# Adafruit_96x64_RGB_OLED_Breakout_v2_0.net
KiCad netlist of a schematic drawn in EAGLE
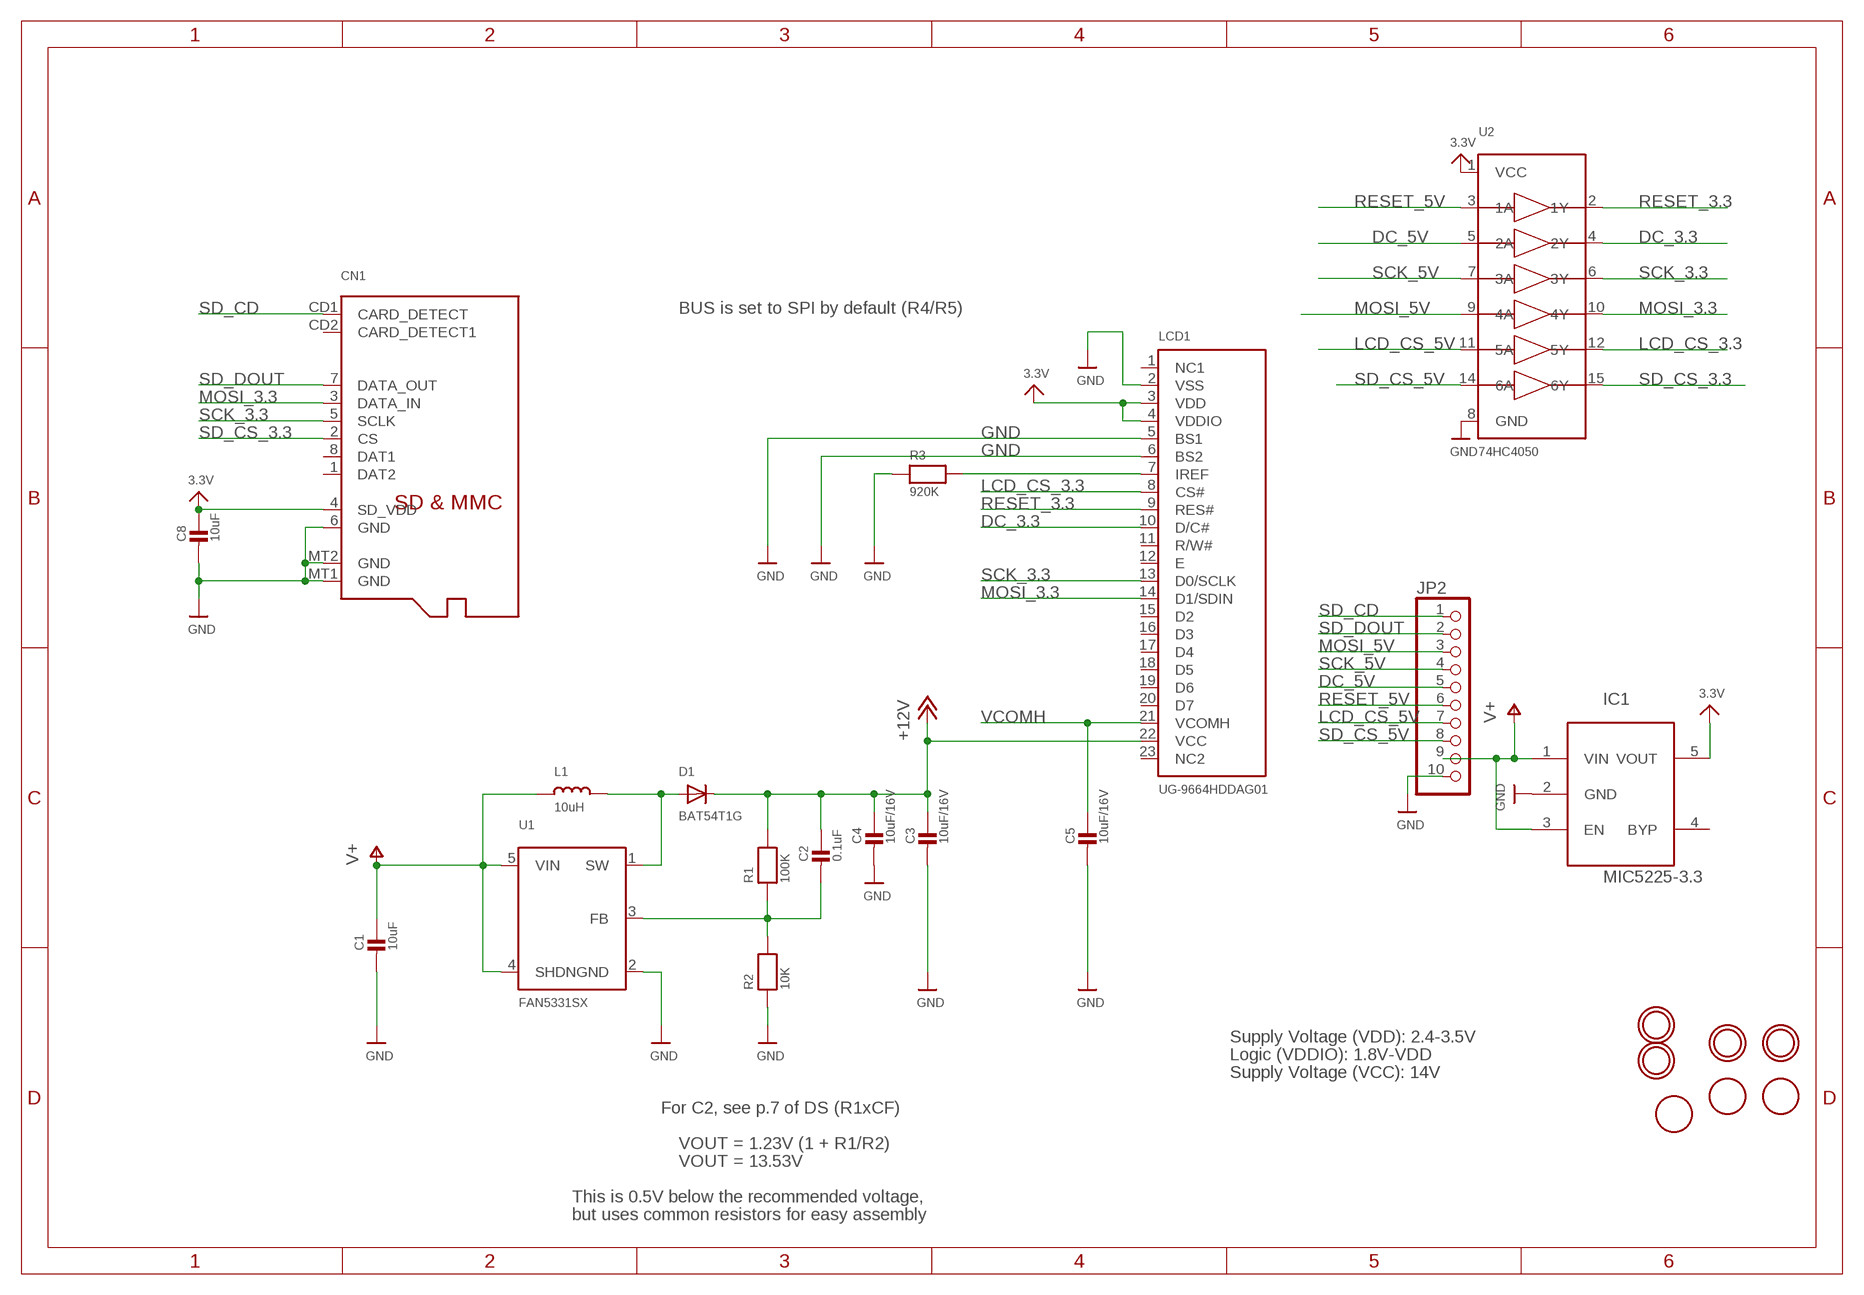
[diagram p0: schematic, sheet 1]

(export (version "E")
  (design (tool "Eeschema 10.0.6"))
  (components
    (comp (ref "C1")
      (value "10uF")
      (footprint "eagle-import:0805")
      (libsource (lib "eagle-import") (part "CAP_CERAMIC0805"))
    )
    (comp (ref "C2")
      (value "0.1uF")
      (footprint "eagle-import:0805")
      (libsource (lib "eagle-import") (part "CAP_CERAMIC0805"))
    )
    (comp (ref "C3")
      (value "10uF/16V")
      (footprint "eagle-import:0805")
      (libsource (lib "eagle-import") (part "CAP_CERAMIC0805"))
    )
    (comp (ref "C4")
      (value "10uF/16V")
      (footprint "eagle-import:0805")
      (libsource (lib "eagle-import") (part "CAP_CERAMIC0805"))
    )
    (comp (ref "C5")
      (value "10uF/16V")
      (footprint "eagle-import:0805")
      (libsource (lib "eagle-import") (part "CAP_CERAMIC0805"))
    )
    (comp (ref "C8")
      (value "10uF")
      (footprint "eagle-import:0805")
      (libsource (lib "eagle-import") (part "CAP_CERAMIC0805"))
    )
    (comp (ref "CN1")
      (value "MICROSD")
      (footprint "eagle-import:MICROSD")
      (libsource (lib "eagle-import") (part "MICROSD"))
    )
    (comp (ref "D1")
      (value "BAT54T1G")
      (footprint "eagle-import:SOD-123")
      (libsource (lib "eagle-import") (part "DIODESOD-123"))
    )
    (comp (ref "IC1")
      (value "MIC5225-3.3")
      (footprint "eagle-import:SOT23-5L")
      (libsource (lib "eagle-import") (part "LP298XS"))
    )
    (comp (ref "JP2")
      (value "HEADER-1X10THICKER")
      (footprint "eagle-import:1X10_ROUND_76")
      (libsource (lib "eagle-import") (part "HEADER-1X10THICKER"))
    )
    (comp (ref "L1")
      (value "10uH")
      (footprint "eagle-import:INDUCTOR_1007")
      (libsource (lib "eagle-import") (part "INDUCTOR"))
    )
    (comp (ref "LCD1")
      (value "UG-9664HDDAG01")
      (footprint "eagle-import:UG-9664HDDAG01_WRAPAROUND")
      (libsource (lib "eagle-import") (part "DISP_OLED_UG-9664HDDAG01WRAPAROUND"))
    )
    (comp (ref "R1")
      (value "100K")
      (footprint "eagle-import:0805")
      (libsource (lib "eagle-import") (part "RESISTOR0805"))
    )
    (comp (ref "R2")
      (value "10K")
      (footprint "eagle-import:0805")
      (libsource (lib "eagle-import") (part "RESISTOR0805"))
    )
    (comp (ref "R3")
      (value "920K")
      (footprint "eagle-import:0805")
      (libsource (lib "eagle-import") (part "RESISTOR0805"))
    )
    (comp (ref "U$9")
      (value "MOUNTINGHOLE2.5")
      (footprint "eagle-import:MOUNTINGHOLE_2.5_PLATED")
      (libsource (lib "eagle-import") (part "MOUNTINGHOLE2.5"))
    )
    (comp (ref "U$10")
      (value "MOUNTINGHOLE2.5")
      (footprint "eagle-import:MOUNTINGHOLE_2.5_PLATED")
      (libsource (lib "eagle-import") (part "MOUNTINGHOLE2.5"))
    )
    (comp (ref "U$11")
      (value "MOUNTINGHOLE2.5")
      (footprint "eagle-import:MOUNTINGHOLE_2.5_PLATED")
      (libsource (lib "eagle-import") (part "MOUNTINGHOLE2.5"))
    )
    (comp (ref "U$12")
      (value "FIDUCIAL")
      (footprint "eagle-import:FIDUCIAL_1MM")
      (libsource (lib "eagle-import") (part "FIDUCIAL"))
    )
    (comp (ref "U$13")
      (value "FIDUCIAL")
      (footprint "eagle-import:FIDUCIAL_1MM")
      (libsource (lib "eagle-import") (part "FIDUCIAL"))
    )
    (comp (ref "U$15")
      (value "MOUNTINGHOLE2.5")
      (footprint "eagle-import:MOUNTINGHOLE_2.5_PLATED")
      (libsource (lib "eagle-import") (part "MOUNTINGHOLE2.5"))
    )
    (comp (ref "U$16")
      (value "FIDUCIAL")
      (footprint "eagle-import:FIDUCIAL_1MM")
      (libsource (lib "eagle-import") (part "FIDUCIAL"))
    )
    (comp (ref "U1")
      (value "FAN5331SX")
      (footprint "eagle-import:SOT23-5")
      (libsource (lib "eagle-import") (part "FAN5331"))
    )
    (comp (ref "U2")
      (value "74HC4050")
      (footprint "eagle-import:SOIC16")
      (libsource (lib "eagle-import") (part "74HC4050D"))
    )
  )
  (nets
    (net (code "1") (name "+12V") (class "Default")
      (node (ref "C2") (pin "1") (pinfunction "P$1_1") (pintype "passive"))
      (node (ref "C3") (pin "1") (pinfunction "P$1_1") (pintype "passive"))
      (node (ref "C4") (pin "1") (pinfunction "P$1_1") (pintype "passive"))
      (node (ref "D1") (pin "C") (pinfunction "C_C") (pintype "passive"))
      (node (ref "LCD1") (pin "22") (pinfunction "VCC_22") (pintype "bidirectional"))
      (node (ref "R1") (pin "2") (pinfunction "2_2") (pintype "passive"))
    )
    (net (code "2") (name "/DC_3.3") (class "Default")
      (node (ref "LCD1") (pin "10") (pinfunction "D/C#_10") (pintype "bidirectional"))
      (node (ref "U2") (pin "4") (pinfunction "2Y_4") (pintype "bidirectional"))
    )
    (net (code "3") (name "/DC_5V") (class "Default")
      (node (ref "JP2") (pin "5") (pinfunction "5_5") (pintype "passive"))
      (node (ref "U2") (pin "5") (pinfunction "2A_5") (pintype "bidirectional"))
    )
    (net (code "4") (name "/LCD_CS_3.3") (class "Default")
      (node (ref "LCD1") (pin "8") (pinfunction "CS#_8") (pintype "bidirectional"))
      (node (ref "U2") (pin "12") (pinfunction "5Y_12") (pintype "bidirectional"))
    )
    (net (code "5") (name "/LCD_CS_5V") (class "Default")
      (node (ref "JP2") (pin "7") (pinfunction "7_7") (pintype "passive"))
      (node (ref "U2") (pin "11") (pinfunction "5A_11") (pintype "bidirectional"))
    )
    (net (code "6") (name "/MOSI_3.3") (class "Default")
      (node (ref "CN1") (pin "3") (pinfunction "DATA_IN_3") (pintype "input"))
      (node (ref "LCD1") (pin "14") (pinfunction "D1/SDIN_14") (pintype "bidirectional"))
      (node (ref "U2") (pin "10") (pinfunction "4Y_10") (pintype "bidirectional"))
    )
    (net (code "7") (name "/MOSI_5V") (class "Default")
      (node (ref "JP2") (pin "3") (pinfunction "3_3") (pintype "passive"))
      (node (ref "U2") (pin "9") (pinfunction "4A_9") (pintype "bidirectional"))
    )
    (net (code "8") (name "/RESET_3.3") (class "Default")
      (node (ref "LCD1") (pin "9") (pinfunction "RES#_9") (pintype "bidirectional"))
      (node (ref "U2") (pin "2") (pinfunction "1Y_2") (pintype "bidirectional"))
    )
    (net (code "9") (name "/RESET_5V") (class "Default")
      (node (ref "JP2") (pin "6") (pinfunction "6_6") (pintype "passive"))
      (node (ref "U2") (pin "3") (pinfunction "1A_3") (pintype "bidirectional"))
    )
    (net (code "10") (name "/SCK_3.3") (class "Default")
      (node (ref "CN1") (pin "5") (pinfunction "SCLK_5") (pintype "input"))
      (node (ref "LCD1") (pin "13") (pinfunction "D0/SCLK_13") (pintype "bidirectional"))
      (node (ref "U2") (pin "6") (pinfunction "3Y_6") (pintype "bidirectional"))
    )
    (net (code "11") (name "/SCK_5V") (class "Default")
      (node (ref "JP2") (pin "4") (pinfunction "4_4") (pintype "passive"))
      (node (ref "U2") (pin "7") (pinfunction "3A_7") (pintype "bidirectional"))
    )
    (net (code "12") (name "/SD_CD") (class "Default")
      (node (ref "CN1") (pin "CD1") (pinfunction "CARD_DETECT_CD1") (pintype "passive"))
      (node (ref "JP2") (pin "1") (pinfunction "1_1") (pintype "passive"))
    )
    (net (code "13") (name "/SD_CS_3.3") (class "Default")
      (node (ref "CN1") (pin "2") (pinfunction "CS_2") (pintype "input"))
      (node (ref "U2") (pin "15") (pinfunction "6Y_15") (pintype "bidirectional"))
    )
    (net (code "14") (name "/SD_CS_5V") (class "Default")
      (node (ref "JP2") (pin "8") (pinfunction "8_8") (pintype "passive"))
      (node (ref "U2") (pin "14") (pinfunction "6A_14") (pintype "bidirectional"))
    )
    (net (code "15") (name "/SD_DOUT") (class "Default")
      (node (ref "CN1") (pin "7") (pinfunction "DATA_OUT_7") (pintype "output"))
      (node (ref "JP2") (pin "2") (pinfunction "2_2") (pintype "passive"))
    )
    (net (code "16") (name "/VCOMH") (class "Default")
      (node (ref "C5") (pin "1") (pinfunction "P$1_1") (pintype "passive"))
      (node (ref "LCD1") (pin "21") (pinfunction "VCOMH_21") (pintype "bidirectional"))
    )
    (net (code "17") (name "3.3V") (class "Default")
      (node (ref "C8") (pin "1") (pinfunction "P$1_1") (pintype "passive"))
      (node (ref "CN1") (pin "4") (pinfunction "SD_VDD_4") (pintype "power_in"))
      (node (ref "IC1") (pin "5") (pinfunction "VOUT_5") (pintype "bidirectional"))
      (node (ref "LCD1") (pin "3") (pinfunction "VDD_3") (pintype "bidirectional"))
      (node (ref "LCD1") (pin "4") (pinfunction "VDDIO_4") (pintype "bidirectional"))
      (node (ref "U2") (pin "1") (pinfunction "VCC_1") (pintype "bidirectional"))
    )
    (net (code "18") (name "GND") (class "Default")
      (node (ref "C1") (pin "2") (pinfunction "P$2_2") (pintype "passive"))
      (node (ref "C3") (pin "2") (pinfunction "P$2_2") (pintype "passive"))
      (node (ref "C4") (pin "2") (pinfunction "P$2_2") (pintype "passive"))
      (node (ref "C5") (pin "2") (pinfunction "P$2_2") (pintype "passive"))
      (node (ref "C8") (pin "2") (pinfunction "P$2_2") (pintype "passive"))
      (node (ref "CN1") (pin "6") (pinfunction "GND_6") (pintype "power_in"))
      (node (ref "CN1") (pin "MT1") (pinfunction "GND_MT1") (pintype "power_in"))
      (node (ref "CN1") (pin "MT2") (pinfunction "GND_MT2") (pintype "power_in"))
      (node (ref "IC1") (pin "2") (pinfunction "GND_2") (pintype "bidirectional"))
      (node (ref "JP2") (pin "10") (pinfunction "10_10") (pintype "passive"))
      (node (ref "LCD1") (pin "2") (pinfunction "VSS_2") (pintype "bidirectional"))
      (node (ref "LCD1") (pin "5") (pinfunction "BS1_5") (pintype "bidirectional"))
      (node (ref "LCD1") (pin "6") (pinfunction "BS2_6") (pintype "bidirectional"))
      (node (ref "R2") (pin "1") (pinfunction "1_1") (pintype "passive"))
      (node (ref "R3") (pin "1") (pinfunction "1_1") (pintype "passive"))
      (node (ref "U1") (pin "2") (pinfunction "GND_2") (pintype "bidirectional"))
      (node (ref "U2") (pin "8") (pinfunction "GND_8") (pintype "bidirectional"))
    )
    (net (code "19") (name "Net-(C2-P$2)") (class "Default")
      (node (ref "C2") (pin "2") (pinfunction "P$2_2") (pintype "passive"))
      (node (ref "R1") (pin "1") (pinfunction "1_1") (pintype "passive"))
      (node (ref "R2") (pin "2") (pinfunction "2_2") (pintype "passive"))
      (node (ref "U1") (pin "3") (pinfunction "FB_3") (pintype "bidirectional"))
    )
    (net (code "20") (name "Net-(L1-2)") (class "Default")
      (node (ref "D1") (pin "A") (pinfunction "A_A") (pintype "passive"))
      (node (ref "L1") (pin "P$2") (pinfunction "2_P$2") (pintype "passive"))
      (node (ref "U1") (pin "1") (pinfunction "SW_1") (pintype "bidirectional"))
    )
    (net (code "21") (name "Net-(LCD1-IREF)") (class "Default")
      (node (ref "LCD1") (pin "7") (pinfunction "IREF_7") (pintype "bidirectional"))
      (node (ref "R3") (pin "2") (pinfunction "2_2") (pintype "passive"))
    )
    (net (code "22") (name "V+") (class "Default")
      (node (ref "C1") (pin "1") (pinfunction "P$1_1") (pintype "passive"))
      (node (ref "IC1") (pin "1") (pinfunction "VIN_1") (pintype "bidirectional"))
      (node (ref "IC1") (pin "3") (pinfunction "EN_3") (pintype "bidirectional"))
      (node (ref "JP2") (pin "9") (pinfunction "9_9") (pintype "passive"))
      (node (ref "L1") (pin "P$1") (pinfunction "1_P$1") (pintype "passive"))
      (node (ref "U1") (pin "4") (pinfunction "SHDN_4") (pintype "bidirectional"))
      (node (ref "U1") (pin "5") (pinfunction "VIN_5") (pintype "bidirectional"))
    )
    (net (code "23") (name "unconnected-(CN1-CARD_DETECT1-PadCD2)") (class "Default")
      (node (ref "CN1") (pin "CD2") (pinfunction "CARD_DETECT1_CD2") (pintype "passive"))
    )
    (net (code "24") (name "unconnected-(CN1-DAT1-Pad8)") (class "Default")
      (node (ref "CN1") (pin "8") (pinfunction "DAT1_8") (pintype "bidirectional"))
    )
    (net (code "25") (name "unconnected-(CN1-DAT2-Pad1)") (class "Default")
      (node (ref "CN1") (pin "1") (pinfunction "DAT2_1") (pintype "bidirectional"))
    )
    (net (code "26") (name "unconnected-(IC1-BYP-Pad4)") (class "Default")
      (node (ref "IC1") (pin "4") (pinfunction "BYP_4") (pintype "bidirectional"))
    )
    (net (code "27") (name "unconnected-(LCD1-D2-Pad15)") (class "Default")
      (node (ref "LCD1") (pin "15") (pinfunction "D2_15") (pintype "bidirectional"))
    )
    (net (code "28") (name "unconnected-(LCD1-D3-Pad16)") (class "Default")
      (node (ref "LCD1") (pin "16") (pinfunction "D3_16") (pintype "bidirectional"))
    )
    (net (code "29") (name "unconnected-(LCD1-D4-Pad17)") (class "Default")
      (node (ref "LCD1") (pin "17") (pinfunction "D4_17") (pintype "bidirectional"))
    )
    (net (code "30") (name "unconnected-(LCD1-D5-Pad18)") (class "Default")
      (node (ref "LCD1") (pin "18") (pinfunction "D5_18") (pintype "bidirectional"))
    )
    (net (code "31") (name "unconnected-(LCD1-D6-Pad19)") (class "Default")
      (node (ref "LCD1") (pin "19") (pinfunction "D6_19") (pintype "bidirectional"))
    )
    (net (code "32") (name "unconnected-(LCD1-D7-Pad20)") (class "Default")
      (node (ref "LCD1") (pin "20") (pinfunction "D7_20") (pintype "bidirectional"))
    )
    (net (code "33") (name "unconnected-(LCD1-E-Pad12)") (class "Default")
      (node (ref "LCD1") (pin "12") (pinfunction "E_12") (pintype "bidirectional"))
    )
    (net (code "34") (name "unconnected-(LCD1-NC1-Pad1)") (class "Default")
      (node (ref "LCD1") (pin "1") (pinfunction "NC1_1") (pintype "no_connect"))
    )
    (net (code "35") (name "unconnected-(LCD1-NC2-Pad23)") (class "Default")
      (node (ref "LCD1") (pin "23") (pinfunction "NC2_23") (pintype "no_connect"))
    )
    (net (code "36") (name "unconnected-(LCD1-R{slash}W#-Pad11)") (class "Default")
      (node (ref "LCD1") (pin "11") (pinfunction "R/W#_11") (pintype "bidirectional"))
    )
  )
)
